# Magnetic-Imaging-Tile.net
KiCad netlist of a schematic drawn in EAGLE
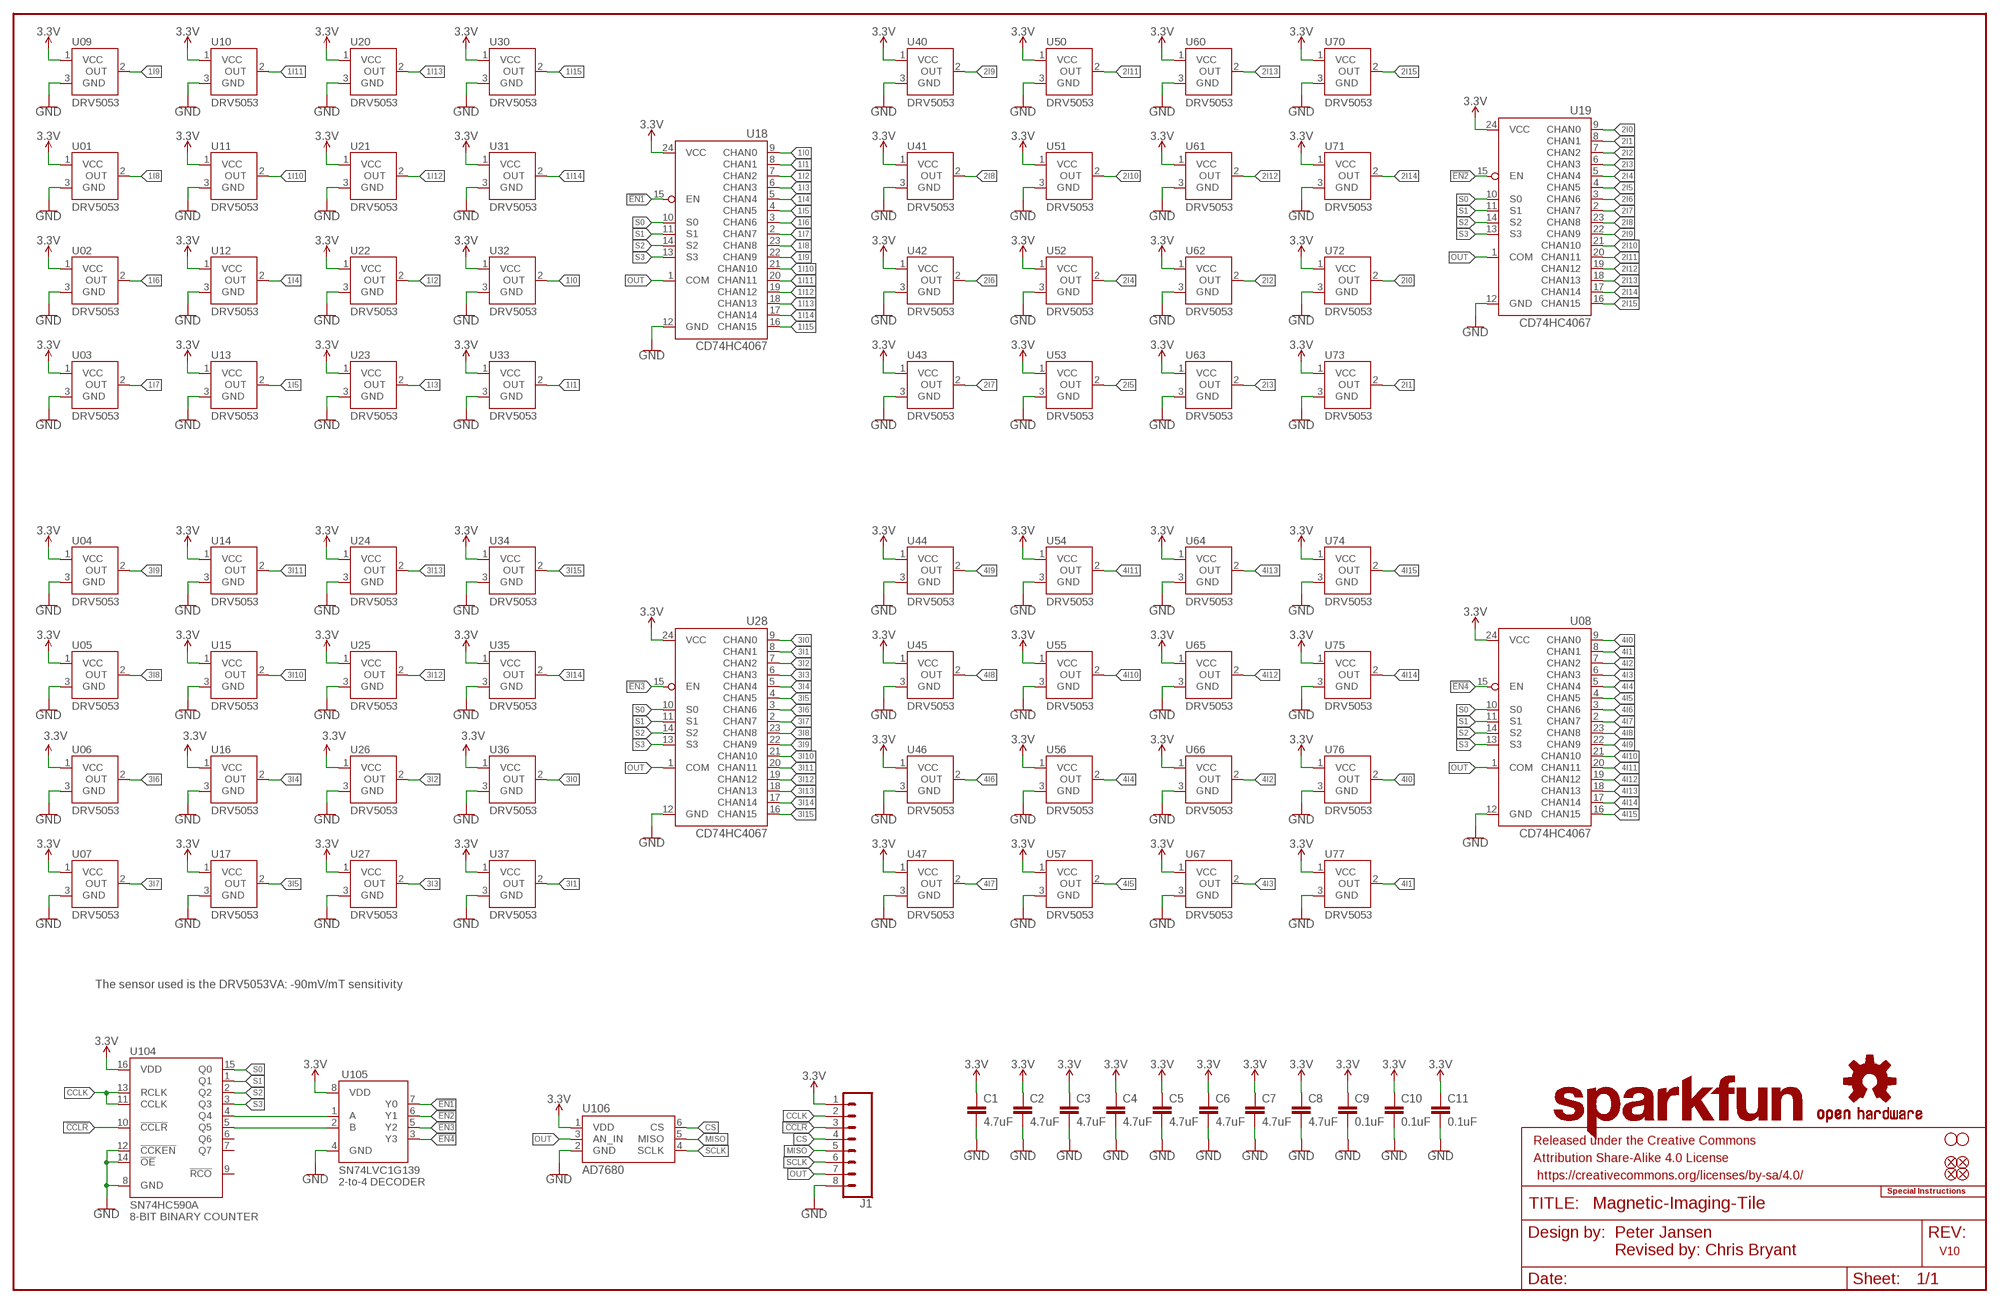
[diagram p0: schematic, sheet 1]

(export (version "E")
  (design (tool "Eeschema 10.0.6"))
  (components
    (comp (ref "C1")
      (value "4.7uF")
      (footprint "eagle-import:0603")
      (libsource (lib "eagle-import") (part "4.7UF-0603-6.3V-(10%)"))
    )
    (comp (ref "C2")
      (value "4.7uF")
      (footprint "eagle-import:0603")
      (libsource (lib "eagle-import") (part "4.7UF-0603-6.3V-(10%)"))
    )
    (comp (ref "C3")
      (value "4.7uF")
      (footprint "eagle-import:0603")
      (libsource (lib "eagle-import") (part "4.7UF-0603-6.3V-(10%)"))
    )
    (comp (ref "C4")
      (value "4.7uF")
      (footprint "eagle-import:0603")
      (libsource (lib "eagle-import") (part "4.7UF-0603-6.3V-(10%)"))
    )
    (comp (ref "C5")
      (value "4.7uF")
      (footprint "eagle-import:0603")
      (libsource (lib "eagle-import") (part "4.7UF-0603-6.3V-(10%)"))
    )
    (comp (ref "C6")
      (value "4.7uF")
      (footprint "eagle-import:0603")
      (libsource (lib "eagle-import") (part "4.7UF-0603-6.3V-(10%)"))
    )
    (comp (ref "C7")
      (value "4.7uF")
      (footprint "eagle-import:0603")
      (libsource (lib "eagle-import") (part "4.7UF-0603-6.3V-(10%)"))
    )
    (comp (ref "C8")
      (value "4.7uF")
      (footprint "eagle-import:0603")
      (libsource (lib "eagle-import") (part "4.7UF-0603-6.3V-(10%)"))
    )
    (comp (ref "C9")
      (value "0.1uF")
      (footprint "eagle-import:0603")
      (libsource (lib "eagle-import") (part "0.1UF-0603-25V-(+80/-20%)"))
    )
    (comp (ref "C10")
      (value "0.1uF")
      (footprint "eagle-import:0603")
      (libsource (lib "eagle-import") (part "0.1UF-0603-25V-(+80/-20%)"))
    )
    (comp (ref "C11")
      (value "0.1uF")
      (footprint "eagle-import:0603")
      (libsource (lib "eagle-import") (part "0.1UF-0603-25V-(+80/-20%)"))
    )
    (comp (ref "FD1")
      (value "FIDUCIALUFIDUCIAL")
      (footprint "eagle-import:FIDUCIAL-MICRO")
      (libsource (lib "eagle-import") (part "FIDUCIALUFIDUCIAL"))
    )
    (comp (ref "FD2")
      (value "FIDUCIALUFIDUCIAL")
      (footprint "eagle-import:FIDUCIAL-MICRO")
      (libsource (lib "eagle-import") (part "FIDUCIALUFIDUCIAL"))
    )
    (comp (ref "FD3")
      (value "FIDUCIALUFIDUCIAL")
      (footprint "eagle-import:FIDUCIAL-MICRO")
      (libsource (lib "eagle-import") (part "FIDUCIALUFIDUCIAL"))
    )
    (comp (ref "FD4")
      (value "FIDUCIALUFIDUCIAL")
      (footprint "eagle-import:FIDUCIAL-MICRO")
      (libsource (lib "eagle-import") (part "FIDUCIALUFIDUCIAL"))
    )
    (comp (ref "FRAME1")
      (value "FRAME-LEDGER")
      (footprint "eagle-import:CREATIVE_COMMONS")
      (libsource (lib "eagle-import") (part "FRAME-LEDGER"))
    )
    (comp (ref "H1")
      (value "STAND-OFF")
      (footprint "eagle-import:STAND-OFF")
      (libsource (lib "eagle-import") (part "STAND-OFF"))
    )
    (comp (ref "H2")
      (value "STAND-OFF")
      (footprint "eagle-import:STAND-OFF")
      (libsource (lib "eagle-import") (part "STAND-OFF"))
    )
    (comp (ref "J1")
      (value "CONN_08LOCK_NO_SILK")
      (footprint "eagle-import:1X08_LOCK_NO_SILK")
      (libsource (lib "eagle-import") (part "CONN_08LOCK_NO_SILK"))
    )
    (comp (ref "LOGO1")
      (value "SPECIAL_INSTRUCTIONS-ORDERING")
      (footprint "eagle-import:ORDERING_INSTRUCTIONS")
      (libsource (lib "eagle-import") (part "SPECIAL_INSTRUCTIONS-ORDERING"))
    )
    (comp (ref "LOGO3")
      (value "SFE_LOGO_NAME.1_INCH")
      (footprint "eagle-import:SFE_LOGO_NAME_.1")
      (libsource (lib "eagle-import") (part "SFE_LOGO_NAME.1_INCH"))
    )
    (comp (ref "LOGO4")
      (value "OSHW-LOGOS")
      (footprint "eagle-import:OSHW-LOGO-S")
      (libsource (lib "eagle-import") (part "OSHW-LOGOS"))
    )
    (comp (ref "U01")
      (value "DRV5053")
      (footprint "eagle-import:SOT23-3")
      (libsource (lib "eagle-import") (part "DRV5053"))
    )
    (comp (ref "U02")
      (value "DRV5053")
      (footprint "eagle-import:SOT23-3")
      (libsource (lib "eagle-import") (part "DRV5053"))
    )
    (comp (ref "U03")
      (value "DRV5053")
      (footprint "eagle-import:SOT23-3")
      (libsource (lib "eagle-import") (part "DRV5053"))
    )
    (comp (ref "U04")
      (value "DRV5053")
      (footprint "eagle-import:SOT23-3")
      (libsource (lib "eagle-import") (part "DRV5053"))
    )
    (comp (ref "U05")
      (value "DRV5053")
      (footprint "eagle-import:SOT23-3")
      (libsource (lib "eagle-import") (part "DRV5053"))
    )
    (comp (ref "U06")
      (value "DRV5053")
      (footprint "eagle-import:SOT23-3")
      (libsource (lib "eagle-import") (part "DRV5053"))
    )
    (comp (ref "U07")
      (value "DRV5053")
      (footprint "eagle-import:SOT23-3")
      (libsource (lib "eagle-import") (part "DRV5053"))
    )
    (comp (ref "U08")
      (value "CD74HC4067")
      (footprint "eagle-import:SSOP24")
      (libsource (lib "eagle-import") (part "744067SM96HC"))
    )
    (comp (ref "U09")
      (value "DRV5053")
      (footprint "eagle-import:SOT23-3")
      (libsource (lib "eagle-import") (part "DRV5053"))
    )
    (comp (ref "U10")
      (value "DRV5053")
      (footprint "eagle-import:SOT23-3")
      (libsource (lib "eagle-import") (part "DRV5053"))
    )
    (comp (ref "U11")
      (value "DRV5053")
      (footprint "eagle-import:SOT23-3")
      (libsource (lib "eagle-import") (part "DRV5053"))
    )
    (comp (ref "U12")
      (value "DRV5053")
      (footprint "eagle-import:SOT23-3")
      (libsource (lib "eagle-import") (part "DRV5053"))
    )
    (comp (ref "U13")
      (value "DRV5053")
      (footprint "eagle-import:SOT23-3")
      (libsource (lib "eagle-import") (part "DRV5053"))
    )
    (comp (ref "U14")
      (value "DRV5053")
      (footprint "eagle-import:SOT23-3")
      (libsource (lib "eagle-import") (part "DRV5053"))
    )
    (comp (ref "U15")
      (value "DRV5053")
      (footprint "eagle-import:SOT23-3")
      (libsource (lib "eagle-import") (part "DRV5053"))
    )
    (comp (ref "U16")
      (value "DRV5053")
      (footprint "eagle-import:SOT23-3")
      (libsource (lib "eagle-import") (part "DRV5053"))
    )
    (comp (ref "U17")
      (value "DRV5053")
      (footprint "eagle-import:SOT23-3")
      (libsource (lib "eagle-import") (part "DRV5053"))
    )
    (comp (ref "U18")
      (value "CD74HC4067")
      (footprint "eagle-import:SSOP24")
      (libsource (lib "eagle-import") (part "744067SM96HC"))
    )
    (comp (ref "U19")
      (value "CD74HC4067")
      (footprint "eagle-import:SSOP24")
      (libsource (lib "eagle-import") (part "744067SM96HC"))
    )
    (comp (ref "U20")
      (value "DRV5053")
      (footprint "eagle-import:SOT23-3")
      (libsource (lib "eagle-import") (part "DRV5053"))
    )
    (comp (ref "U21")
      (value "DRV5053")
      (footprint "eagle-import:SOT23-3")
      (libsource (lib "eagle-import") (part "DRV5053"))
    )
    (comp (ref "U22")
      (value "DRV5053")
      (footprint "eagle-import:SOT23-3")
      (libsource (lib "eagle-import") (part "DRV5053"))
    )
    (comp (ref "U23")
      (value "DRV5053")
      (footprint "eagle-import:SOT23-3")
      (libsource (lib "eagle-import") (part "DRV5053"))
    )
    (comp (ref "U24")
      (value "DRV5053")
      (footprint "eagle-import:SOT23-3")
      (libsource (lib "eagle-import") (part "DRV5053"))
    )
    (comp (ref "U25")
      (value "DRV5053")
      (footprint "eagle-import:SOT23-3")
      (libsource (lib "eagle-import") (part "DRV5053"))
    )
    (comp (ref "U26")
      (value "DRV5053")
      (footprint "eagle-import:SOT23-3")
      (libsource (lib "eagle-import") (part "DRV5053"))
    )
    (comp (ref "U27")
      (value "DRV5053")
      (footprint "eagle-import:SOT23-3")
      (libsource (lib "eagle-import") (part "DRV5053"))
    )
    (comp (ref "U28")
      (value "CD74HC4067")
      (footprint "eagle-import:SSOP24")
      (libsource (lib "eagle-import") (part "744067SM96HC"))
    )
    (comp (ref "U30")
      (value "DRV5053")
      (footprint "eagle-import:SOT23-3")
      (libsource (lib "eagle-import") (part "DRV5053"))
    )
    (comp (ref "U31")
      (value "DRV5053")
      (footprint "eagle-import:SOT23-3")
      (libsource (lib "eagle-import") (part "DRV5053"))
    )
    (comp (ref "U32")
      (value "DRV5053")
      (footprint "eagle-import:SOT23-3")
      (libsource (lib "eagle-import") (part "DRV5053"))
    )
    (comp (ref "U33")
      (value "DRV5053")
      (footprint "eagle-import:SOT23-3")
      (libsource (lib "eagle-import") (part "DRV5053"))
    )
    (comp (ref "U34")
      (value "DRV5053")
      (footprint "eagle-import:SOT23-3")
      (libsource (lib "eagle-import") (part "DRV5053"))
    )
    (comp (ref "U35")
      (value "DRV5053")
      (footprint "eagle-import:SOT23-3")
      (libsource (lib "eagle-import") (part "DRV5053"))
    )
    (comp (ref "U36")
      (value "DRV5053")
      (footprint "eagle-import:SOT23-3")
      (libsource (lib "eagle-import") (part "DRV5053"))
    )
    (comp (ref "U37")
      (value "DRV5053")
      (footprint "eagle-import:SOT23-3")
      (libsource (lib "eagle-import") (part "DRV5053"))
    )
    (comp (ref "U40")
      (value "DRV5053")
      (footprint "eagle-import:SOT23-3")
      (libsource (lib "eagle-import") (part "DRV5053"))
    )
    (comp (ref "U41")
      (value "DRV5053")
      (footprint "eagle-import:SOT23-3")
      (libsource (lib "eagle-import") (part "DRV5053"))
    )
    (comp (ref "U42")
      (value "DRV5053")
      (footprint "eagle-import:SOT23-3")
      (libsource (lib "eagle-import") (part "DRV5053"))
    )
    (comp (ref "U43")
      (value "DRV5053")
      (footprint "eagle-import:SOT23-3")
      (libsource (lib "eagle-import") (part "DRV5053"))
    )
    (comp (ref "U44")
      (value "DRV5053")
      (footprint "eagle-import:SOT23-3")
      (libsource (lib "eagle-import") (part "DRV5053"))
    )
    (comp (ref "U45")
      (value "DRV5053")
      (footprint "eagle-import:SOT23-3")
      (libsource (lib "eagle-import") (part "DRV5053"))
    )
    (comp (ref "U46")
      (value "DRV5053")
      (footprint "eagle-import:SOT23-3")
      (libsource (lib "eagle-import") (part "DRV5053"))
    )
    (comp (ref "U47")
      (value "DRV5053")
      (footprint "eagle-import:SOT23-3")
      (libsource (lib "eagle-import") (part "DRV5053"))
    )
    (comp (ref "U50")
      (value "DRV5053")
      (footprint "eagle-import:SOT23-3")
      (libsource (lib "eagle-import") (part "DRV5053"))
    )
    (comp (ref "U51")
      (value "DRV5053")
      (footprint "eagle-import:SOT23-3")
      (libsource (lib "eagle-import") (part "DRV5053"))
    )
    (comp (ref "U52")
      (value "DRV5053")
      (footprint "eagle-import:SOT23-3")
      (libsource (lib "eagle-import") (part "DRV5053"))
    )
    (comp (ref "U53")
      (value "DRV5053")
      (footprint "eagle-import:SOT23-3")
      (libsource (lib "eagle-import") (part "DRV5053"))
    )
    (comp (ref "U54")
      (value "DRV5053")
      (footprint "eagle-import:SOT23-3")
      (libsource (lib "eagle-import") (part "DRV5053"))
    )
    (comp (ref "U55")
      (value "DRV5053")
      (footprint "eagle-import:SOT23-3")
      (libsource (lib "eagle-import") (part "DRV5053"))
    )
    (comp (ref "U56")
      (value "DRV5053")
      (footprint "eagle-import:SOT23-3")
      (libsource (lib "eagle-import") (part "DRV5053"))
    )
    (comp (ref "U57")
      (value "DRV5053")
      (footprint "eagle-import:SOT23-3")
      (libsource (lib "eagle-import") (part "DRV5053"))
    )
    (comp (ref "U60")
      (value "DRV5053")
      (footprint "eagle-import:SOT23-3")
      (libsource (lib "eagle-import") (part "DRV5053"))
    )
    (comp (ref "U61")
      (value "DRV5053")
      (footprint "eagle-import:SOT23-3")
      (libsource (lib "eagle-import") (part "DRV5053"))
    )
    (comp (ref "U62")
      (value "DRV5053")
      (footprint "eagle-import:SOT23-3")
      (libsource (lib "eagle-import") (part "DRV5053"))
    )
    (comp (ref "U63")
      (value "DRV5053")
      (footprint "eagle-import:SOT23-3")
      (libsource (lib "eagle-import") (part "DRV5053"))
    )
    (comp (ref "U64")
      (value "DRV5053")
      (footprint "eagle-import:SOT23-3")
      (libsource (lib "eagle-import") (part "DRV5053"))
    )
    (comp (ref "U65")
      (value "DRV5053")
      (footprint "eagle-import:SOT23-3")
      (libsource (lib "eagle-import") (part "DRV5053"))
    )
    (comp (ref "U66")
      (value "DRV5053")
      (footprint "eagle-import:SOT23-3")
      (libsource (lib "eagle-import") (part "DRV5053"))
    )
    (comp (ref "U67")
      (value "DRV5053")
      (footprint "eagle-import:SOT23-3")
      (libsource (lib "eagle-import") (part "DRV5053"))
    )
    (comp (ref "U70")
      (value "DRV5053")
      (footprint "eagle-import:SOT23-3")
      (libsource (lib "eagle-import") (part "DRV5053"))
    )
    (comp (ref "U71")
      (value "DRV5053")
      (footprint "eagle-import:SOT23-3")
      (libsource (lib "eagle-import") (part "DRV5053"))
    )
    (comp (ref "U72")
      (value "DRV5053")
      (footprint "eagle-import:SOT23-3")
      (libsource (lib "eagle-import") (part "DRV5053"))
    )
    (comp (ref "U73")
      (value "DRV5053")
      (footprint "eagle-import:SOT23-3")
      (libsource (lib "eagle-import") (part "DRV5053"))
    )
    (comp (ref "U74")
      (value "DRV5053")
      (footprint "eagle-import:SOT23-3")
      (libsource (lib "eagle-import") (part "DRV5053"))
    )
    (comp (ref "U75")
      (value "DRV5053")
      (footprint "eagle-import:SOT23-3")
      (libsource (lib "eagle-import") (part "DRV5053"))
    )
    (comp (ref "U76")
      (value "DRV5053")
      (footprint "eagle-import:SOT23-3")
      (libsource (lib "eagle-import") (part "DRV5053"))
    )
    (comp (ref "U77")
      (value "DRV5053")
      (footprint "eagle-import:SOT23-3")
      (libsource (lib "eagle-import") (part "DRV5053"))
    )
    (comp (ref "U104")
      (value "SN74HC590A")
      (footprint "eagle-import:SO16")
      (libsource (lib "eagle-import") (part "SN74HC590A"))
    )
    (comp (ref "U105")
      (value "SN74LVC1G139")
      (footprint "eagle-import:SM8")
      (libsource (lib "eagle-import") (part "SN74LVC1G139"))
    )
    (comp (ref "U106")
      (value "AD7680")
      (footprint "eagle-import:SOT23-6")
      (libsource (lib "eagle-import") (part "AD7940"))
    )
  )
  (nets
    (net (code "1") (name "/~{CCLR}") (class "Default")
      (node (ref "J1") (pin "3") (pinfunction "3_3") (pintype "passive"))
      (node (ref "U104") (pin "10") (pinfunction "~{CCLR}_10") (pintype "bidirectional"))
    )
    (net (code "2") (name "/~{EN1}") (class "Default")
      (node (ref "U105") (pin "7") (pinfunction "Y0_7") (pintype "bidirectional"))
      (node (ref "U18") (pin "15") (pinfunction "EN_15") (pintype "input"))
    )
    (net (code "3") (name "/~{EN2}") (class "Default")
      (node (ref "U105") (pin "6") (pinfunction "Y1_6") (pintype "bidirectional"))
      (node (ref "U19") (pin "15") (pinfunction "EN_15") (pintype "input"))
    )
    (net (code "4") (name "/~{EN3}") (class "Default")
      (node (ref "U105") (pin "5") (pinfunction "Y2_5") (pintype "bidirectional"))
      (node (ref "U28") (pin "15") (pinfunction "EN_15") (pintype "input"))
    )
    (net (code "5") (name "/~{EN4}") (class "Default")
      (node (ref "U08") (pin "15") (pinfunction "EN_15") (pintype "input"))
      (node (ref "U105") (pin "3") (pinfunction "Y3_3") (pintype "bidirectional"))
    )
    (net (code "6") (name "1I0") (class "Default")
      (node (ref "U18") (pin "9") (pinfunction "CHAN0_9") (pintype "bidirectional"))
      (node (ref "U32") (pin "2") (pinfunction "OUT_2") (pintype "bidirectional"))
    )
    (net (code "7") (name "1I1") (class "Default")
      (node (ref "U18") (pin "8") (pinfunction "CHAN1_8") (pintype "bidirectional"))
      (node (ref "U33") (pin "2") (pinfunction "OUT_2") (pintype "bidirectional"))
    )
    (net (code "8") (name "1I2") (class "Default")
      (node (ref "U18") (pin "7") (pinfunction "CHAN2_7") (pintype "bidirectional"))
      (node (ref "U22") (pin "2") (pinfunction "OUT_2") (pintype "bidirectional"))
    )
    (net (code "9") (name "1I3") (class "Default")
      (node (ref "U18") (pin "6") (pinfunction "CHAN3_6") (pintype "bidirectional"))
      (node (ref "U23") (pin "2") (pinfunction "OUT_2") (pintype "bidirectional"))
    )
    (net (code "10") (name "1I4") (class "Default")
      (node (ref "U12") (pin "2") (pinfunction "OUT_2") (pintype "bidirectional"))
      (node (ref "U18") (pin "5") (pinfunction "CHAN4_5") (pintype "bidirectional"))
    )
    (net (code "11") (name "1I5") (class "Default")
      (node (ref "U13") (pin "2") (pinfunction "OUT_2") (pintype "bidirectional"))
      (node (ref "U18") (pin "4") (pinfunction "CHAN5_4") (pintype "bidirectional"))
    )
    (net (code "12") (name "1I6") (class "Default")
      (node (ref "U02") (pin "2") (pinfunction "OUT_2") (pintype "bidirectional"))
      (node (ref "U18") (pin "3") (pinfunction "CHAN6_3") (pintype "bidirectional"))
    )
    (net (code "13") (name "1I7") (class "Default")
      (node (ref "U03") (pin "2") (pinfunction "OUT_2") (pintype "bidirectional"))
      (node (ref "U18") (pin "2") (pinfunction "CHAN7_2") (pintype "bidirectional"))
    )
    (net (code "14") (name "1I8") (class "Default")
      (node (ref "U01") (pin "2") (pinfunction "OUT_2") (pintype "bidirectional"))
      (node (ref "U18") (pin "23") (pinfunction "CHAN8_23") (pintype "bidirectional"))
    )
    (net (code "15") (name "1I9") (class "Default")
      (node (ref "U09") (pin "2") (pinfunction "OUT_2") (pintype "bidirectional"))
      (node (ref "U18") (pin "22") (pinfunction "CHAN9_22") (pintype "bidirectional"))
    )
    (net (code "16") (name "1I10") (class "Default")
      (node (ref "U11") (pin "2") (pinfunction "OUT_2") (pintype "bidirectional"))
      (node (ref "U18") (pin "21") (pinfunction "CHAN10_21") (pintype "bidirectional"))
    )
    (net (code "17") (name "1I11") (class "Default")
      (node (ref "U10") (pin "2") (pinfunction "OUT_2") (pintype "bidirectional"))
      (node (ref "U18") (pin "20") (pinfunction "CHAN11_20") (pintype "bidirectional"))
    )
    (net (code "18") (name "1I12") (class "Default")
      (node (ref "U18") (pin "19") (pinfunction "CHAN12_19") (pintype "bidirectional"))
      (node (ref "U21") (pin "2") (pinfunction "OUT_2") (pintype "bidirectional"))
    )
    (net (code "19") (name "1I13") (class "Default")
      (node (ref "U18") (pin "18") (pinfunction "CHAN13_18") (pintype "bidirectional"))
      (node (ref "U20") (pin "2") (pinfunction "OUT_2") (pintype "bidirectional"))
    )
    (net (code "20") (name "1I14") (class "Default")
      (node (ref "U18") (pin "17") (pinfunction "CHAN14_17") (pintype "bidirectional"))
      (node (ref "U31") (pin "2") (pinfunction "OUT_2") (pintype "bidirectional"))
    )
    (net (code "21") (name "1I15") (class "Default")
      (node (ref "U18") (pin "16") (pinfunction "CHAN15_16") (pintype "bidirectional"))
      (node (ref "U30") (pin "2") (pinfunction "OUT_2") (pintype "bidirectional"))
    )
    (net (code "22") (name "2I0") (class "Default")
      (node (ref "U19") (pin "9") (pinfunction "CHAN0_9") (pintype "bidirectional"))
      (node (ref "U72") (pin "2") (pinfunction "OUT_2") (pintype "bidirectional"))
    )
    (net (code "23") (name "2I1") (class "Default")
      (node (ref "U19") (pin "8") (pinfunction "CHAN1_8") (pintype "bidirectional"))
      (node (ref "U73") (pin "2") (pinfunction "OUT_2") (pintype "bidirectional"))
    )
    (net (code "24") (name "2I2") (class "Default")
      (node (ref "U19") (pin "7") (pinfunction "CHAN2_7") (pintype "bidirectional"))
      (node (ref "U62") (pin "2") (pinfunction "OUT_2") (pintype "bidirectional"))
    )
    (net (code "25") (name "2I3") (class "Default")
      (node (ref "U19") (pin "6") (pinfunction "CHAN3_6") (pintype "bidirectional"))
      (node (ref "U63") (pin "2") (pinfunction "OUT_2") (pintype "bidirectional"))
    )
    (net (code "26") (name "2I4") (class "Default")
      (node (ref "U19") (pin "5") (pinfunction "CHAN4_5") (pintype "bidirectional"))
      (node (ref "U52") (pin "2") (pinfunction "OUT_2") (pintype "bidirectional"))
    )
    (net (code "27") (name "2I5") (class "Default")
      (node (ref "U19") (pin "4") (pinfunction "CHAN5_4") (pintype "bidirectional"))
      (node (ref "U53") (pin "2") (pinfunction "OUT_2") (pintype "bidirectional"))
    )
    (net (code "28") (name "2I6") (class "Default")
      (node (ref "U19") (pin "3") (pinfunction "CHAN6_3") (pintype "bidirectional"))
      (node (ref "U42") (pin "2") (pinfunction "OUT_2") (pintype "bidirectional"))
    )
    (net (code "29") (name "2I7") (class "Default")
      (node (ref "U19") (pin "2") (pinfunction "CHAN7_2") (pintype "bidirectional"))
      (node (ref "U43") (pin "2") (pinfunction "OUT_2") (pintype "bidirectional"))
    )
    (net (code "30") (name "2I8") (class "Default")
      (node (ref "U19") (pin "23") (pinfunction "CHAN8_23") (pintype "bidirectional"))
      (node (ref "U41") (pin "2") (pinfunction "OUT_2") (pintype "bidirectional"))
    )
    (net (code "31") (name "2I9") (class "Default")
      (node (ref "U19") (pin "22") (pinfunction "CHAN9_22") (pintype "bidirectional"))
      (node (ref "U40") (pin "2") (pinfunction "OUT_2") (pintype "bidirectional"))
    )
    (net (code "32") (name "2I10") (class "Default")
      (node (ref "U19") (pin "21") (pinfunction "CHAN10_21") (pintype "bidirectional"))
      (node (ref "U51") (pin "2") (pinfunction "OUT_2") (pintype "bidirectional"))
    )
    (net (code "33") (name "2I11") (class "Default")
      (node (ref "U19") (pin "20") (pinfunction "CHAN11_20") (pintype "bidirectional"))
      (node (ref "U50") (pin "2") (pinfunction "OUT_2") (pintype "bidirectional"))
    )
    (net (code "34") (name "2I12") (class "Default")
      (node (ref "U19") (pin "19") (pinfunction "CHAN12_19") (pintype "bidirectional"))
      (node (ref "U61") (pin "2") (pinfunction "OUT_2") (pintype "bidirectional"))
    )
    (net (code "35") (name "2I13") (class "Default")
      (node (ref "U19") (pin "18") (pinfunction "CHAN13_18") (pintype "bidirectional"))
      (node (ref "U60") (pin "2") (pinfunction "OUT_2") (pintype "bidirectional"))
    )
    (net (code "36") (name "2I14") (class "Default")
      (node (ref "U19") (pin "17") (pinfunction "CHAN14_17") (pintype "bidirectional"))
      (node (ref "U71") (pin "2") (pinfunction "OUT_2") (pintype "bidirectional"))
    )
    (net (code "37") (name "2I15") (class "Default")
      (node (ref "U19") (pin "16") (pinfunction "CHAN15_16") (pintype "bidirectional"))
      (node (ref "U70") (pin "2") (pinfunction "OUT_2") (pintype "bidirectional"))
    )
    (net (code "38") (name "3.3V") (class "Default")
      (node (ref "C1") (pin "1") (pinfunction "1_1") (pintype "passive"))
      (node (ref "C10") (pin "1") (pinfunction "1_1") (pintype "passive"))
      (node (ref "C11") (pin "1") (pinfunction "1_1") (pintype "passive"))
      (node (ref "C2") (pin "1") (pinfunction "1_1") (pintype "passive"))
      (node (ref "C3") (pin "1") (pinfunction "1_1") (pintype "passive"))
      (node (ref "C4") (pin "1") (pinfunction "1_1") (pintype "passive"))
      (node (ref "C5") (pin "1") (pinfunction "1_1") (pintype "passive"))
      (node (ref "C6") (pin "1") (pinfunction "1_1") (pintype "passive"))
      (node (ref "C7") (pin "1") (pinfunction "1_1") (pintype "passive"))
      (node (ref "C8") (pin "1") (pinfunction "1_1") (pintype "passive"))
      (node (ref "C9") (pin "1") (pinfunction "1_1") (pintype "passive"))
      (node (ref "J1") (pin "1") (pinfunction "1_1") (pintype "passive"))
      (node (ref "U01") (pin "1") (pinfunction "VCC_1") (pintype "bidirectional"))
      (node (ref "U02") (pin "1") (pinfunction "VCC_1") (pintype "bidirectional"))
      (node (ref "U03") (pin "1") (pinfunction "VCC_1") (pintype "bidirectional"))
      (node (ref "U04") (pin "1") (pinfunction "VCC_1") (pintype "bidirectional"))
      (node (ref "U05") (pin "1") (pinfunction "VCC_1") (pintype "bidirectional"))
      (node (ref "U06") (pin "1") (pinfunction "VCC_1") (pintype "bidirectional"))
      (node (ref "U07") (pin "1") (pinfunction "VCC_1") (pintype "bidirectional"))
      (node (ref "U08") (pin "24") (pinfunction "VCC_24") (pintype "bidirectional"))
      (node (ref "U09") (pin "1") (pinfunction "VCC_1") (pintype "bidirectional"))
      (node (ref "U10") (pin "1") (pinfunction "VCC_1") (pintype "bidirectional"))
      (node (ref "U104") (pin "16") (pinfunction "VDD_16") (pintype "bidirectional"))
      (node (ref "U105") (pin "8") (pinfunction "VDD_8") (pintype "bidirectional"))
      (node (ref "U106") (pin "1") (pinfunction "VDD_1") (pintype "bidirectional"))
      (node (ref "U11") (pin "1") (pinfunction "VCC_1") (pintype "bidirectional"))
      (node (ref "U12") (pin "1") (pinfunction "VCC_1") (pintype "bidirectional"))
      (node (ref "U13") (pin "1") (pinfunction "VCC_1") (pintype "bidirectional"))
      (node (ref "U14") (pin "1") (pinfunction "VCC_1") (pintype "bidirectional"))
      (node (ref "U15") (pin "1") (pinfunction "VCC_1") (pintype "bidirectional"))
      (node (ref "U16") (pin "1") (pinfunction "VCC_1") (pintype "bidirectional"))
      (node (ref "U17") (pin "1") (pinfunction "VCC_1") (pintype "bidirectional"))
      (node (ref "U18") (pin "24") (pinfunction "VCC_24") (pintype "bidirectional"))
      (node (ref "U19") (pin "24") (pinfunction "VCC_24") (pintype "bidirectional"))
      (node (ref "U20") (pin "1") (pinfunction "VCC_1") (pintype "bidirectional"))
      (node (ref "U21") (pin "1") (pinfunction "VCC_1") (pintype "bidirectional"))
      (node (ref "U22") (pin "1") (pinfunction "VCC_1") (pintype "bidirectional"))
      (node (ref "U23") (pin "1") (pinfunction "VCC_1") (pintype "bidirectional"))
      (node (ref "U24") (pin "1") (pinfunction "VCC_1") (pintype "bidirectional"))
      (node (ref "U25") (pin "1") (pinfunction "VCC_1") (pintype "bidirectional"))
      (node (ref "U26") (pin "1") (pinfunction "VCC_1") (pintype "bidirectional"))
      (node (ref "U27") (pin "1") (pinfunction "VCC_1") (pintype "bidirectional"))
      (node (ref "U28") (pin "24") (pinfunction "VCC_24") (pintype "bidirectional"))
      (node (ref "U30") (pin "1") (pinfunction "VCC_1") (pintype "bidirectional"))
      (node (ref "U31") (pin "1") (pinfunction "VCC_1") (pintype "bidirectional"))
      (node (ref "U32") (pin "1") (pinfunction "VCC_1") (pintype "bidirectional"))
      (node (ref "U33") (pin "1") (pinfunction "VCC_1") (pintype "bidirectional"))
      (node (ref "U34") (pin "1") (pinfunction "VCC_1") (pintype "bidirectional"))
      (node (ref "U35") (pin "1") (pinfunction "VCC_1") (pintype "bidirectional"))
      (node (ref "U36") (pin "1") (pinfunction "VCC_1") (pintype "bidirectional"))
      (node (ref "U37") (pin "1") (pinfunction "VCC_1") (pintype "bidirectional"))
      (node (ref "U40") (pin "1") (pinfunction "VCC_1") (pintype "bidirectional"))
      (node (ref "U41") (pin "1") (pinfunction "VCC_1") (pintype "bidirectional"))
      (node (ref "U42") (pin "1") (pinfunction "VCC_1") (pintype "bidirectional"))
      (node (ref "U43") (pin "1") (pinfunction "VCC_1") (pintype "bidirectional"))
      (node (ref "U44") (pin "1") (pinfunction "VCC_1") (pintype "bidirectional"))
      (node (ref "U45") (pin "1") (pinfunction "VCC_1") (pintype "bidirectional"))
      (node (ref "U46") (pin "1") (pinfunction "VCC_1") (pintype "bidirectional"))
      (node (ref "U47") (pin "1") (pinfunction "VCC_1") (pintype "bidirectional"))
      (node (ref "U50") (pin "1") (pinfunction "VCC_1") (pintype "bidirectional"))
      (node (ref "U51") (pin "1") (pinfunction "VCC_1") (pintype "bidirectional"))
      (node (ref "U52") (pin "1") (pinfunction "VCC_1") (pintype "bidirectional"))
      (node (ref "U53") (pin "1") (pinfunction "VCC_1") (pintype "bidirectional"))
      (node (ref "U54") (pin "1") (pinfunction "VCC_1") (pintype "bidirectional"))
      (node (ref "U55") (pin "1") (pinfunction "VCC_1") (pintype "bidirectional"))
      (node (ref "U56") (pin "1") (pinfunction "VCC_1") (pintype "bidirectional"))
      (node (ref "U57") (pin "1") (pinfunction "VCC_1") (pintype "bidirectional"))
      (node (ref "U60") (pin "1") (pinfunction "VCC_1") (pintype "bidirectional"))
      (node (ref "U61") (pin "1") (pinfunction "VCC_1") (pintype "bidirectional"))
      (node (ref "U62") (pin "1") (pinfunction "VCC_1") (pintype "bidirectional"))
      (node (ref "U63") (pin "1") (pinfunction "VCC_1") (pintype "bidirectional"))
      (node (ref "U64") (pin "1") (pinfunction "VCC_1") (pintype "bidirectional"))
      (node (ref "U65") (pin "1") (pinfunction "VCC_1") (pintype "bidirectional"))
      (node (ref "U66") (pin "1") (pinfunction "VCC_1") (pintype "bidirectional"))
      (node (ref "U67") (pin "1") (pinfunction "VCC_1") (pintype "bidirectional"))
      (node (ref "U70") (pin "1") (pinfunction "VCC_1") (pintype "bidirectional"))
      (node (ref "U71") (pin "1") (pinfunction "VCC_1") (pintype "bidirectional"))
      (node (ref "U72") (pin "1") (pinfunction "VCC_1") (pintype "bidirectional"))
      (node (ref "U73") (pin "1") (pinfunction "VCC_1") (pintype "bidirectional"))
      (node (ref "U74") (pin "1") (pinfunction "VCC_1") (pintype "bidirectional"))
      (node (ref "U75") (pin "1") (pinfunction "VCC_1") (pintype "bidirectional"))
      (node (ref "U76") (pin "1") (pinfunction "VCC_1") (pintype "bidirectional"))
      (node (ref "U77") (pin "1") (pinfunction "VCC_1") (pintype "bidirectional"))
    )
    (net (code "39") (name "3I0") (class "Default")
      (node (ref "U28") (pin "9") (pinfunction "CHAN0_9") (pintype "bidirectional"))
      (node (ref "U36") (pin "2") (pinfunction "OUT_2") (pintype "bidirectional"))
    )
    (net (code "40") (name "3I1") (class "Default")
      (node (ref "U28") (pin "8") (pinfunction "CHAN1_8") (pintype "bidirectional"))
      (node (ref "U37") (pin "2") (pinfunction "OUT_2") (pintype "bidirectional"))
    )
    (net (code "41") (name "3I2") (class "Default")
      (node (ref "U26") (pin "2") (pinfunction "OUT_2") (pintype "bidirectional"))
      (node (ref "U28") (pin "7") (pinfunction "CHAN2_7") (pintype "bidirectional"))
    )
    (net (code "42") (name "3I3") (class "Default")
      (node (ref "U27") (pin "2") (pinfunction "OUT_2") (pintype "bidirectional"))
      (node (ref "U28") (pin "6") (pinfunction "CHAN3_6") (pintype "bidirectional"))
    )
    (net (code "43") (name "3I4") (class "Default")
      (node (ref "U16") (pin "2") (pinfunction "OUT_2") (pintype "bidirectional"))
      (node (ref "U28") (pin "5") (pinfunction "CHAN4_5") (pintype "bidirectional"))
    )
    (net (code "44") (name "3I5") (class "Default")
      (node (ref "U17") (pin "2") (pinfunction "OUT_2") (pintype "bidirectional"))
      (node (ref "U28") (pin "4") (pinfunction "CHAN5_4") (pintype "bidirectional"))
    )
    (net (code "45") (name "3I6") (class "Default")
      (node (ref "U06") (pin "2") (pinfunction "OUT_2") (pintype "bidirectional"))
      (node (ref "U28") (pin "3") (pinfunction "CHAN6_3") (pintype "bidirectional"))
    )
    (net (code "46") (name "3I7") (class "Default")
      (node (ref "U07") (pin "2") (pinfunction "OUT_2") (pintype "bidirectional"))
      (node (ref "U28") (pin "2") (pinfunction "CHAN7_2") (pintype "bidirectional"))
    )
    (net (code "47") (name "3I8") (class "Default")
      (node (ref "U05") (pin "2") (pinfunction "OUT_2") (pintype "bidirectional"))
      (node (ref "U28") (pin "23") (pinfunction "CHAN8_23") (pintype "bidirectional"))
    )
    (net (code "48") (name "3I9") (class "Default")
      (node (ref "U04") (pin "2") (pinfunction "OUT_2") (pintype "bidirectional"))
      (node (ref "U28") (pin "22") (pinfunction "CHAN9_22") (pintype "bidirectional"))
    )
    (net (code "49") (name "3I10") (class "Default")
      (node (ref "U15") (pin "2") (pinfunction "OUT_2") (pintype "bidirectional"))
      (node (ref "U28") (pin "21") (pinfunction "CHAN10_21") (pintype "bidirectional"))
    )
    (net (code "50") (name "3I11") (class "Default")
      (node (ref "U14") (pin "2") (pinfunction "OUT_2") (pintype "bidirectional"))
      (node (ref "U28") (pin "20") (pinfunction "CHAN11_20") (pintype "bidirectional"))
    )
    (net (code "51") (name "3I12") (class "Default")
      (node (ref "U25") (pin "2") (pinfunction "OUT_2") (pintype "bidirectional"))
      (node (ref "U28") (pin "19") (pinfunction "CHAN12_19") (pintype "bidirectional"))
    )
    (net (code "52") (name "3I13") (class "Default")
      (node (ref "U24") (pin "2") (pinfunction "OUT_2") (pintype "bidirectional"))
      (node (ref "U28") (pin "18") (pinfunction "CHAN13_18") (pintype "bidirectional"))
    )
    (net (code "53") (name "3I14") (class "Default")
      (node (ref "U28") (pin "17") (pinfunction "CHAN14_17") (pintype "bidirectional"))
      (node (ref "U35") (pin "2") (pinfunction "OUT_2") (pintype "bidirectional"))
    )
    (net (code "54") (name "3I15") (class "Default")
      (node (ref "U28") (pin "16") (pinfunction "CHAN15_16") (pintype "bidirectional"))
      (node (ref "U34") (pin "2") (pinfunction "OUT_2") (pintype "bidirectional"))
    )
    (net (code "55") (name "4I0") (class "Default")
      (node (ref "U08") (pin "9") (pinfunction "CHAN0_9") (pintype "bidirectional"))
      (node (ref "U76") (pin "2") (pinfunction "OUT_2") (pintype "bidirectional"))
    )
    (net (code "56") (name "4I1") (class "Default")
      (node (ref "U08") (pin "8") (pinfunction "CHAN1_8") (pintype "bidirectional"))
      (node (ref "U77") (pin "2") (pinfunction "OUT_2") (pintype "bidirectional"))
    )
    (net (code "57") (name "4I2") (class "Default")
      (node (ref "U08") (pin "7") (pinfunction "CHAN2_7") (pintype "bidirectional"))
      (node (ref "U66") (pin "2") (pinfunction "OUT_2") (pintype "bidirectional"))
    )
    (net (code "58") (name "4I3") (class "Default")
      (node (ref "U08") (pin "6") (pinfunction "CHAN3_6") (pintype "bidirectional"))
      (node (ref "U67") (pin "2") (pinfunction "OUT_2") (pintype "bidirectional"))
    )
    (net (code "59") (name "4I4") (class "Default")
      (node (ref "U08") (pin "5") (pinfunction "CHAN4_5") (pintype "bidirectional"))
      (node (ref "U56") (pin "2") (pinfunction "OUT_2") (pintype "bidirectional"))
    )
    (net (code "60") (name "4I5") (class "Default")
      (node (ref "U08") (pin "4") (pinfunction "CHAN5_4") (pintype "bidirectional"))
      (node (ref "U57") (pin "2") (pinfunction "OUT_2") (pintype "bidirectional"))
    )
    (net (code "61") (name "4I6") (class "Default")
      (node (ref "U08") (pin "3") (pinfunction "CHAN6_3") (pintype "bidirectional"))
      (node (ref "U46") (pin "2") (pinfunction "OUT_2") (pintype "bidirectional"))
    )
    (net (code "62") (name "4I7") (class "Default")
      (node (ref "U08") (pin "2") (pinfunction "CHAN7_2") (pintype "bidirectional"))
      (node (ref "U47") (pin "2") (pinfunction "OUT_2") (pintype "bidirectional"))
    )
    (net (code "63") (name "4I8") (class "Default")
      (node (ref "U08") (pin "23") (pinfunction "CHAN8_23") (pintype "bidirectional"))
      (node (ref "U45") (pin "2") (pinfunction "OUT_2") (pintype "bidirectional"))
    )
    (net (code "64") (name "4I9") (class "Default")
      (node (ref "U08") (pin "22") (pinfunction "CHAN9_22") (pintype "bidirectional"))
      (node (ref "U44") (pin "2") (pinfunction "OUT_2") (pintype "bidirectional"))
    )
    (net (code "65") (name "4I10") (class "Default")
      (node (ref "U08") (pin "21") (pinfunction "CHAN10_21") (pintype "bidirectional"))
      (node (ref "U55") (pin "2") (pinfunction "OUT_2") (pintype "bidirectional"))
    )
    (net (code "66") (name "4I11") (class "Default")
      (node (ref "U08") (pin "20") (pinfunction "CHAN11_20") (pintype "bidirectional"))
      (node (ref "U54") (pin "2") (pinfunction "OUT_2") (pintype "bidirectional"))
    )
    (net (code "67") (name "4I12") (class "Default")
      (node (ref "U08") (pin "19") (pinfunction "CHAN12_19") (pintype "bidirectional"))
      (node (ref "U65") (pin "2") (pinfunction "OUT_2") (pintype "bidirectional"))
    )
    (net (code "68") (name "4I13") (class "Default")
      (node (ref "U08") (pin "18") (pinfunction "CHAN13_18") (pintype "bidirectional"))
      (node (ref "U64") (pin "2") (pinfunction "OUT_2") (pintype "bidirectional"))
    )
    (net (code "69") (name "4I14") (class "Default")
      (node (ref "U08") (pin "17") (pinfunction "CHAN14_17") (pintype "bidirectional"))
      (node (ref "U75") (pin "2") (pinfunction "OUT_2") (pintype "bidirectional"))
    )
    (net (code "70") (name "4I15") (class "Default")
      (node (ref "U08") (pin "16") (pinfunction "CHAN15_16") (pintype "bidirectional"))
      (node (ref "U74") (pin "2") (pinfunction "OUT_2") (pintype "bidirectional"))
    )
    (net (code "71") (name "CCLK") (class "Default")
      (node (ref "J1") (pin "2") (pinfunction "2_2") (pintype "passive"))
      (node (ref "U104") (pin "11") (pinfunction "CCLK_11") (pintype "bidirectional"))
      (node (ref "U104") (pin "13") (pinfunction "RCLK_13") (pintype "bidirectional"))
    )
    (net (code "72") (name "CS") (class "Default")
      (node (ref "J1") (pin "4") (pinfunction "4_4") (pintype "passive"))
      (node (ref "U106") (pin "6") (pinfunction "CS_6") (pintype "bidirectional"))
    )
    (net (code "73") (name "GND") (class "Default")
      (node (ref "C1") (pin "2") (pinfunction "2_2") (pintype "passive"))
      (node (ref "C10") (pin "2") (pinfunction "2_2") (pintype "passive"))
      (node (ref "C11") (pin "2") (pinfunction "2_2") (pintype "passive"))
      (node (ref "C2") (pin "2") (pinfunction "2_2") (pintype "passive"))
      (node (ref "C3") (pin "2") (pinfunction "2_2") (pintype "passive"))
      (node (ref "C4") (pin "2") (pinfunction "2_2") (pintype "passive"))
      (node (ref "C5") (pin "2") (pinfunction "2_2") (pintype "passive"))
      (node (ref "C6") (pin "2") (pinfunction "2_2") (pintype "passive"))
      (node (ref "C7") (pin "2") (pinfunction "2_2") (pintype "passive"))
      (node (ref "C8") (pin "2") (pinfunction "2_2") (pintype "passive"))
      (node (ref "C9") (pin "2") (pinfunction "2_2") (pintype "passive"))
      (node (ref "J1") (pin "8") (pinfunction "8_8") (pintype "passive"))
      (node (ref "U01") (pin "3") (pinfunction "GND_3") (pintype "bidirectional"))
      (node (ref "U02") (pin "3") (pinfunction "GND_3") (pintype "bidirectional"))
      (node (ref "U03") (pin "3") (pinfunction "GND_3") (pintype "bidirectional"))
      (node (ref "U04") (pin "3") (pinfunction "GND_3") (pintype "bidirectional"))
      (node (ref "U05") (pin "3") (pinfunction "GND_3") (pintype "bidirectional"))
      (node (ref "U06") (pin "3") (pinfunction "GND_3") (pintype "bidirectional"))
      (node (ref "U07") (pin "3") (pinfunction "GND_3") (pintype "bidirectional"))
      (node (ref "U08") (pin "12") (pinfunction "GND_12") (pintype "bidirectional"))
      (node (ref "U09") (pin "3") (pinfunction "GND_3") (pintype "bidirectional"))
      (node (ref "U10") (pin "3") (pinfunction "GND_3") (pintype "bidirectional"))
      (node (ref "U104") (pin "12") (pinfunction "~{CCKEN}_12") (pintype "bidirectional"))
      (node (ref "U104") (pin "14") (pinfunction "~{OE}_14") (pintype "bidirectional"))
      (node (ref "U104") (pin "8") (pinfunction "GND_8") (pintype "bidirectional"))
      (node (ref "U105") (pin "4") (pinfunction "GND_4") (pintype "bidirectional"))
      (node (ref "U106") (pin "2") (pinfunction "GND_2") (pintype "bidirectional"))
      (node (ref "U11") (pin "3") (pinfunction "GND_3") (pintype "bidirectional"))
      (node (ref "U12") (pin "3") (pinfunction "GND_3") (pintype "bidirectional"))
      (node (ref "U13") (pin "3") (pinfunction "GND_3") (pintype "bidirectional"))
      (node (ref "U14") (pin "3") (pinfunction "GND_3") (pintype "bidirectional"))
      (node (ref "U15") (pin "3") (pinfunction "GND_3") (pintype "bidirectional"))
      (node (ref "U16") (pin "3") (pinfunction "GND_3") (pintype "bidirectional"))
      (node (ref "U17") (pin "3") (pinfunction "GND_3") (pintype "bidirectional"))
      (node (ref "U18") (pin "12") (pinfunction "GND_12") (pintype "bidirectional"))
      (node (ref "U19") (pin "12") (pinfunction "GND_12") (pintype "bidirectional"))
      (node (ref "U20") (pin "3") (pinfunction "GND_3") (pintype "bidirectional"))
      (node (ref "U21") (pin "3") (pinfunction "GND_3") (pintype "bidirectional"))
      (node (ref "U22") (pin "3") (pinfunction "GND_3") (pintype "bidirectional"))
      (node (ref "U23") (pin "3") (pinfunction "GND_3") (pintype "bidirectional"))
      (node (ref "U24") (pin "3") (pinfunction "GND_3") (pintype "bidirectional"))
      (node (ref "U25") (pin "3") (pinfunction "GND_3") (pintype "bidirectional"))
      (node (ref "U26") (pin "3") (pinfunction "GND_3") (pintype "bidirectional"))
      (node (ref "U27") (pin "3") (pinfunction "GND_3") (pintype "bidirectional"))
      (node (ref "U28") (pin "12") (pinfunction "GND_12") (pintype "bidirectional"))
      (node (ref "U30") (pin "3") (pinfunction "GND_3") (pintype "bidirectional"))
      (node (ref "U31") (pin "3") (pinfunction "GND_3") (pintype "bidirectional"))
      (node (ref "U32") (pin "3") (pinfunction "GND_3") (pintype "bidirectional"))
      (node (ref "U33") (pin "3") (pinfunction "GND_3") (pintype "bidirectional"))
      (node (ref "U34") (pin "3") (pinfunction "GND_3") (pintype "bidirectional"))
      (node (ref "U35") (pin "3") (pinfunction "GND_3") (pintype "bidirectional"))
      (node (ref "U36") (pin "3") (pinfunction "GND_3") (pintype "bidirectional"))
      (node (ref "U37") (pin "3") (pinfunction "GND_3") (pintype "bidirectional"))
      (node (ref "U40") (pin "3") (pinfunction "GND_3") (pintype "bidirectional"))
      (node (ref "U41") (pin "3") (pinfunction "GND_3") (pintype "bidirectional"))
      (node (ref "U42") (pin "3") (pinfunction "GND_3") (pintype "bidirectional"))
      (node (ref "U43") (pin "3") (pinfunction "GND_3") (pintype "bidirectional"))
      (node (ref "U44") (pin "3") (pinfunction "GND_3") (pintype "bidirectional"))
      (node (ref "U45") (pin "3") (pinfunction "GND_3") (pintype "bidirectional"))
      (node (ref "U46") (pin "3") (pinfunction "GND_3") (pintype "bidirectional"))
      (node (ref "U47") (pin "3") (pinfunction "GND_3") (pintype "bidirectional"))
      (node (ref "U50") (pin "3") (pinfunction "GND_3") (pintype "bidirectional"))
      (node (ref "U51") (pin "3") (pinfunction "GND_3") (pintype "bidirectional"))
      (node (ref "U52") (pin "3") (pinfunction "GND_3") (pintype "bidirectional"))
      (node (ref "U53") (pin "3") (pinfunction "GND_3") (pintype "bidirectional"))
      (node (ref "U54") (pin "3") (pinfunction "GND_3") (pintype "bidirectional"))
      (node (ref "U55") (pin "3") (pinfunction "GND_3") (pintype "bidirectional"))
      (node (ref "U56") (pin "3") (pinfunction "GND_3") (pintype "bidirectional"))
      (node (ref "U57") (pin "3") (pinfunction "GND_3") (pintype "bidirectional"))
      (node (ref "U60") (pin "3") (pinfunction "GND_3") (pintype "bidirectional"))
      (node (ref "U61") (pin "3") (pinfunction "GND_3") (pintype "bidirectional"))
      (node (ref "U62") (pin "3") (pinfunction "GND_3") (pintype "bidirectional"))
      (node (ref "U63") (pin "3") (pinfunction "GND_3") (pintype "bidirectional"))
      (node (ref "U64") (pin "3") (pinfunction "GND_3") (pintype "bidirectional"))
      (node (ref "U65") (pin "3") (pinfunction "GND_3") (pintype "bidirectional"))
      (node (ref "U66") (pin "3") (pinfunction "GND_3") (pintype "bidirectional"))
      (node (ref "U67") (pin "3") (pinfunction "GND_3") (pintype "bidirectional"))
      (node (ref "U70") (pin "3") (pinfunction "GND_3") (pintype "bidirectional"))
      (node (ref "U71") (pin "3") (pinfunction "GND_3") (pintype "bidirectional"))
      (node (ref "U72") (pin "3") (pinfunction "GND_3") (pintype "bidirectional"))
      (node (ref "U73") (pin "3") (pinfunction "GND_3") (pintype "bidirectional"))
      (node (ref "U74") (pin "3") (pinfunction "GND_3") (pintype "bidirectional"))
      (node (ref "U75") (pin "3") (pinfunction "GND_3") (pintype "bidirectional"))
      (node (ref "U76") (pin "3") (pinfunction "GND_3") (pintype "bidirectional"))
      (node (ref "U77") (pin "3") (pinfunction "GND_3") (pintype "bidirectional"))
    )
    (net (code "74") (name "MISO") (class "Default")
      (node (ref "J1") (pin "5") (pinfunction "5_5") (pintype "passive"))
      (node (ref "U106") (pin "5") (pinfunction "MISO_5") (pintype "bidirectional"))
    )
    (net (code "75") (name "Net-(U104-Q4)") (class "Default")
      (node (ref "U104") (pin "4") (pinfunction "Q4_4") (pintype "bidirectional"))
      (node (ref "U105") (pin "1") (pinfunction "A_1") (pintype "bidirectional"))
    )
    (net (code "76") (name "Net-(U104-Q5)") (class "Default")
      (node (ref "U104") (pin "5") (pinfunction "Q5_5") (pintype "bidirectional"))
      (node (ref "U105") (pin "2") (pinfunction "B_2") (pintype "bidirectional"))
    )
    (net (code "77") (name "OUT") (class "Default")
      (node (ref "J1") (pin "7") (pinfunction "7_7") (pintype "passive"))
      (node (ref "U08") (pin "1") (pinfunction "COM_1") (pintype "bidirectional"))
      (node (ref "U106") (pin "3") (pinfunction "AN_IN_3") (pintype "bidirectional"))
      (node (ref "U18") (pin "1") (pinfunction "COM_1") (pintype "bidirectional"))
      (node (ref "U19") (pin "1") (pinfunction "COM_1") (pintype "bidirectional"))
      (node (ref "U28") (pin "1") (pinfunction "COM_1") (pintype "bidirectional"))
    )
    (net (code "78") (name "S0") (class "Default")
      (node (ref "U08") (pin "10") (pinfunction "S0_10") (pintype "input"))
      (node (ref "U104") (pin "15") (pinfunction "Q0_15") (pintype "bidirectional"))
      (node (ref "U18") (pin "10") (pinfunction "S0_10") (pintype "input"))
      (node (ref "U19") (pin "10") (pinfunction "S0_10") (pintype "input"))
      (node (ref "U28") (pin "10") (pinfunction "S0_10") (pintype "input"))
    )
    (net (code "79") (name "S1") (class "Default")
      (node (ref "U08") (pin "11") (pinfunction "S1_11") (pintype "input"))
      (node (ref "U104") (pin "1") (pinfunction "Q1_1") (pintype "bidirectional"))
      (node (ref "U18") (pin "11") (pinfunction "S1_11") (pintype "input"))
      (node (ref "U19") (pin "11") (pinfunction "S1_11") (pintype "input"))
      (node (ref "U28") (pin "11") (pinfunction "S1_11") (pintype "input"))
    )
    (net (code "80") (name "S2") (class "Default")
      (node (ref "U08") (pin "14") (pinfunction "S2_14") (pintype "input"))
      (node (ref "U104") (pin "2") (pinfunction "Q2_2") (pintype "bidirectional"))
      (node (ref "U18") (pin "14") (pinfunction "S2_14") (pintype "input"))
      (node (ref "U19") (pin "14") (pinfunction "S2_14") (pintype "input"))
      (node (ref "U28") (pin "14") (pinfunction "S2_14") (pintype "input"))
    )
    (net (code "81") (name "S3") (class "Default")
      (node (ref "U08") (pin "13") (pinfunction "S3_13") (pintype "input"))
      (node (ref "U104") (pin "3") (pinfunction "Q3_3") (pintype "bidirectional"))
      (node (ref "U18") (pin "13") (pinfunction "S3_13") (pintype "input"))
      (node (ref "U19") (pin "13") (pinfunction "S3_13") (pintype "input"))
      (node (ref "U28") (pin "13") (pinfunction "S3_13") (pintype "input"))
    )
    (net (code "82") (name "SCLK") (class "Default")
      (node (ref "J1") (pin "6") (pinfunction "6_6") (pintype "passive"))
      (node (ref "U106") (pin "4") (pinfunction "SCLK_4") (pintype "bidirectional"))
    )
    (net (code "83") (name "unconnected-(U104-Q6-Pad6)") (class "Default")
      (node (ref "U104") (pin "6") (pinfunction "Q6_6") (pintype "bidirectional"))
    )
    (net (code "84") (name "unconnected-(U104-Q7-Pad7)") (class "Default")
      (node (ref "U104") (pin "7") (pinfunction "Q7_7") (pintype "bidirectional"))
    )
    (net (code "85") (name "unconnected-(U104-~{RCO}-Pad9)") (class "Default")
      (node (ref "U104") (pin "9") (pinfunction "~{RCO}_9") (pintype "bidirectional"))
    )
  )
)
